# tinyblick2.net
KiCad netlist of a schematic drawn in EAGLE
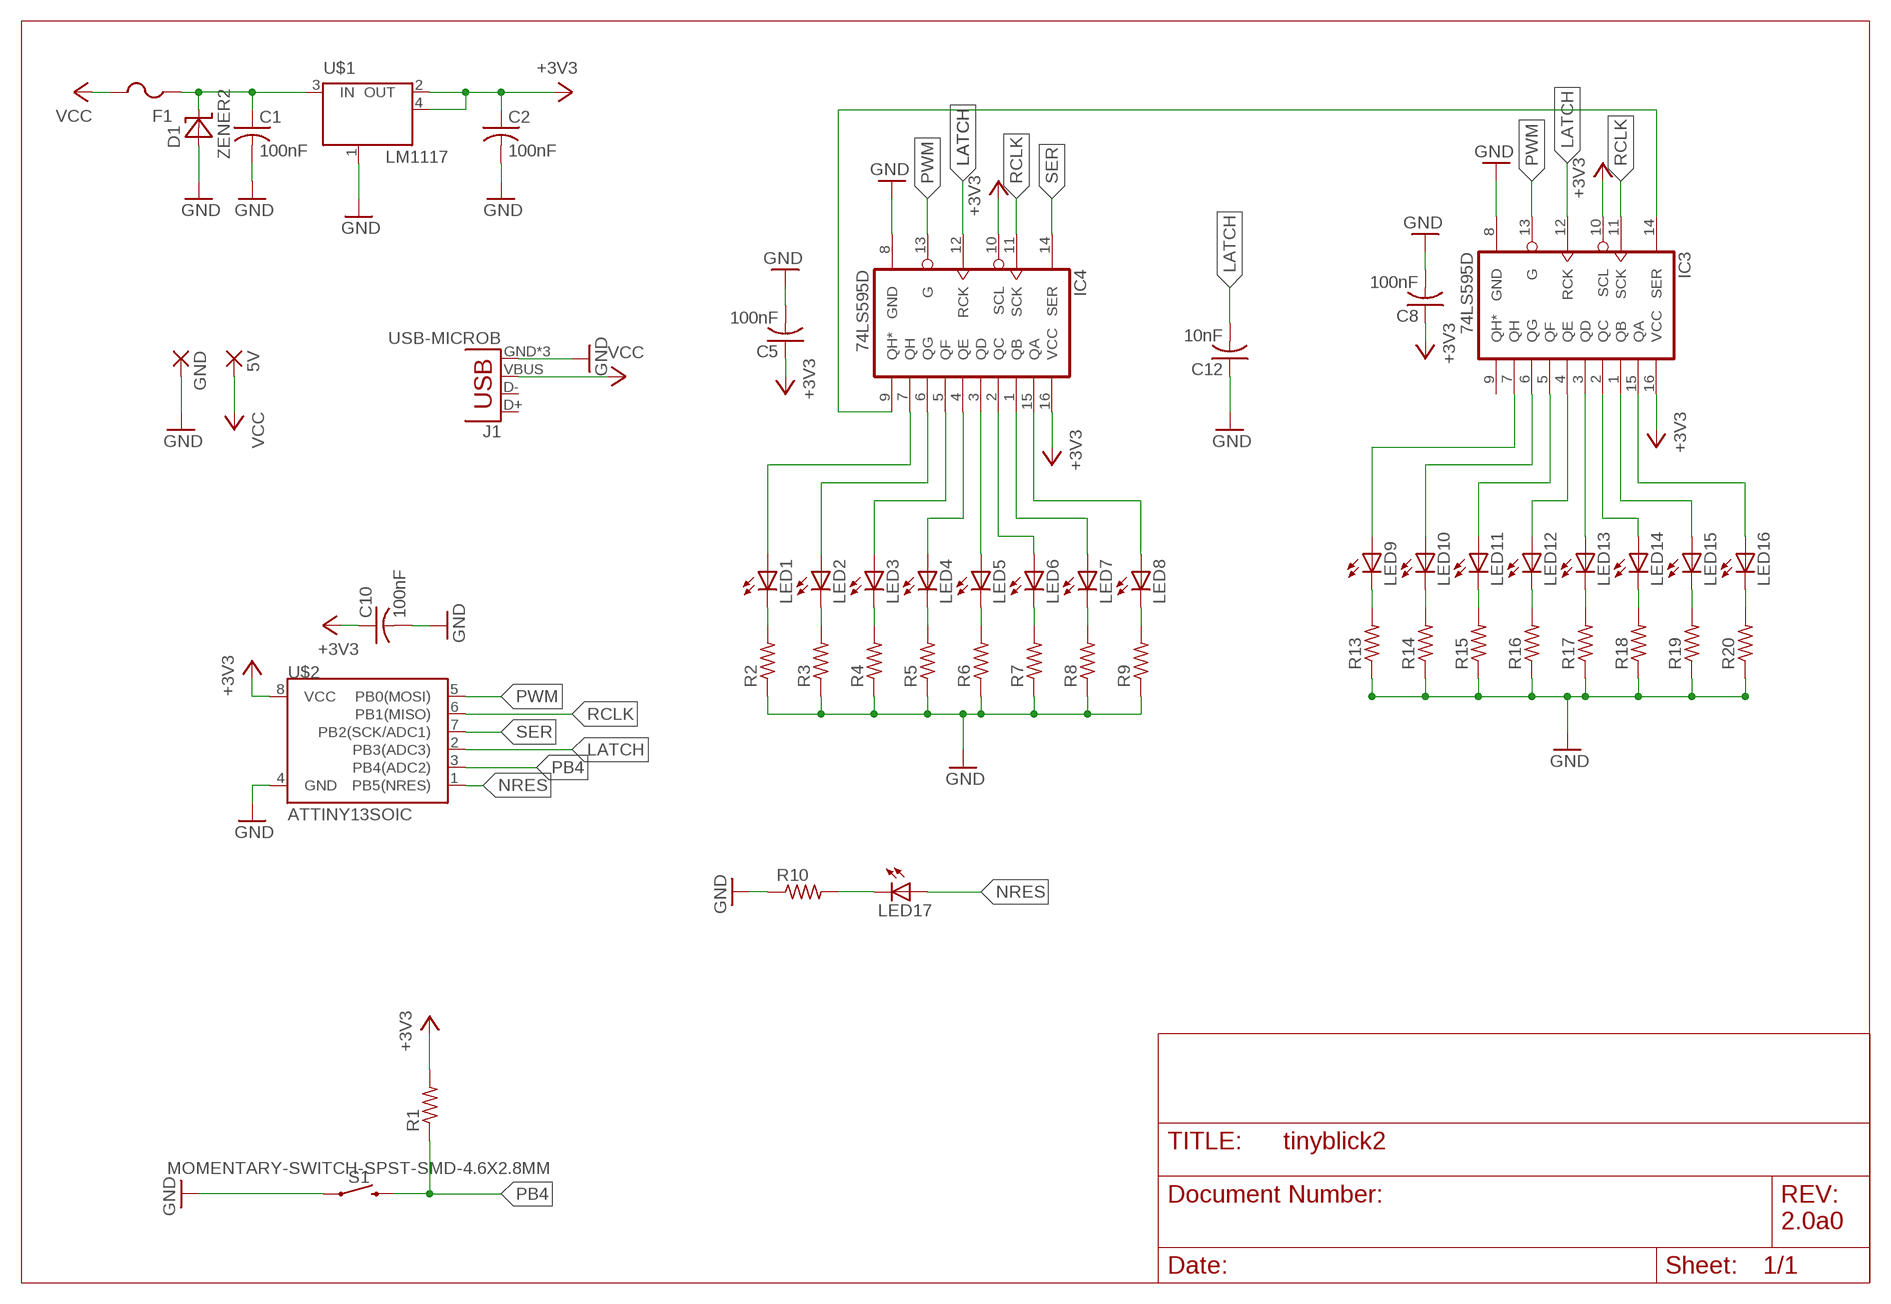
[diagram p0: schematic, sheet 1]

(export (version "E")
  (design (tool "Eeschema 10.0.6"))
  (components
    (comp (ref "5V")
      (value "WIREPADSMD2,54-5,08")
      (footprint "eagle-import:SMD2,54-5,08")
      (libsource (lib "eagle-import") (part "WIREPADSMD2,54-5,08"))
    )
    (comp (ref "C1")
      (value "100nF")
      (footprint "eagle-import:C0603")
      (libsource (lib "eagle-import") (part "C-USC0603"))
    )
    (comp (ref "C2")
      (value "100nF")
      (footprint "eagle-import:C0603")
      (libsource (lib "eagle-import") (part "C-USC0603"))
    )
    (comp (ref "C5")
      (value "100nF")
      (footprint "eagle-import:C0603")
      (libsource (lib "eagle-import") (part "C-USC0603"))
    )
    (comp (ref "C8")
      (value "100nF")
      (footprint "eagle-import:C0603")
      (libsource (lib "eagle-import") (part "C-USC0603"))
    )
    (comp (ref "C10")
      (value "100nF")
      (footprint "eagle-import:C0603")
      (libsource (lib "eagle-import") (part "C-USC0603"))
    )
    (comp (ref "C12")
      (value "10nF")
      (footprint "eagle-import:C0603")
      (libsource (lib "eagle-import") (part "C-USC0603"))
    )
    (comp (ref "D1")
      (value "ZENER2")
      (footprint "eagle-import:SOD123")
      (libsource (lib "eagle-import") (part "ZENER2"))
    )
    (comp (ref "F1")
      (value "PTCFUSE-1206")
      (footprint "eagle-import:R1206")
      (libsource (lib "eagle-import") (part "PTCFUSE-1206"))
    )
    (comp (ref "GND")
      (value "WIREPADSMD2,54-5,08")
      (footprint "eagle-import:SMD2,54-5,08")
      (libsource (lib "eagle-import") (part "WIREPADSMD2,54-5,08"))
    )
    (comp (ref "IC3")
      (value "74LS595D")
      (footprint "eagle-import:SO16")
      (libsource (lib "eagle-import") (part "74595DLS"))
    )
    (comp (ref "IC4")
      (value "74LS595D")
      (footprint "eagle-import:SO16")
      (fields (field (name "SPICEPREFIX") "X"))
      (libsource (lib "eagle-import") (part "74595DLS"))
    )
    (comp (ref "J1")
      (value "USB-MICROB")
      (footprint "eagle-import:USB-MICROB")
      (libsource (lib "eagle-import") (part "USB-MICROB"))
    )
    (comp (ref "LED1")
      (value "LEDCHIP-LED0603")
      (footprint "eagle-import:CHIP-LED0603")
      (libsource (lib "eagle-import") (part "LEDCHIP-LED0603"))
    )
    (comp (ref "LED2")
      (value "LEDCHIP-LED0603")
      (footprint "eagle-import:CHIP-LED0603")
      (libsource (lib "eagle-import") (part "LEDCHIP-LED0603"))
    )
    (comp (ref "LED3")
      (value "LEDCHIP-LED0603")
      (footprint "eagle-import:CHIP-LED0603")
      (libsource (lib "eagle-import") (part "LEDCHIP-LED0603"))
    )
    (comp (ref "LED4")
      (value "LEDCHIP-LED0603")
      (footprint "eagle-import:CHIP-LED0603")
      (libsource (lib "eagle-import") (part "LEDCHIP-LED0603"))
    )
    (comp (ref "LED5")
      (value "LEDCHIP-LED0603")
      (footprint "eagle-import:CHIP-LED0603")
      (libsource (lib "eagle-import") (part "LEDCHIP-LED0603"))
    )
    (comp (ref "LED6")
      (value "LEDCHIP-LED0603")
      (footprint "eagle-import:CHIP-LED0603")
      (libsource (lib "eagle-import") (part "LEDCHIP-LED0603"))
    )
    (comp (ref "LED7")
      (value "LEDCHIP-LED0603")
      (footprint "eagle-import:CHIP-LED0603")
      (libsource (lib "eagle-import") (part "LEDCHIP-LED0603"))
    )
    (comp (ref "LED8")
      (value "LEDCHIP-LED0603")
      (footprint "eagle-import:CHIP-LED0603")
      (libsource (lib "eagle-import") (part "LEDCHIP-LED0603"))
    )
    (comp (ref "LED9")
      (value "LEDCHIP-LED0603")
      (footprint "eagle-import:CHIP-LED0603")
      (libsource (lib "eagle-import") (part "LEDCHIP-LED0603"))
    )
    (comp (ref "LED10")
      (value "LEDCHIP-LED0603")
      (footprint "eagle-import:CHIP-LED0603")
      (libsource (lib "eagle-import") (part "LEDCHIP-LED0603"))
    )
    (comp (ref "LED11")
      (value "LEDCHIP-LED0603")
      (footprint "eagle-import:CHIP-LED0603")
      (libsource (lib "eagle-import") (part "LEDCHIP-LED0603"))
    )
    (comp (ref "LED12")
      (value "LEDCHIP-LED0603")
      (footprint "eagle-import:CHIP-LED0603")
      (libsource (lib "eagle-import") (part "LEDCHIP-LED0603"))
    )
    (comp (ref "LED13")
      (value "LEDCHIP-LED0603")
      (footprint "eagle-import:CHIP-LED0603")
      (libsource (lib "eagle-import") (part "LEDCHIP-LED0603"))
    )
    (comp (ref "LED14")
      (value "LEDCHIP-LED0603")
      (footprint "eagle-import:CHIP-LED0603")
      (libsource (lib "eagle-import") (part "LEDCHIP-LED0603"))
    )
    (comp (ref "LED15")
      (value "LEDCHIP-LED0603")
      (footprint "eagle-import:CHIP-LED0603")
      (libsource (lib "eagle-import") (part "LEDCHIP-LED0603"))
    )
    (comp (ref "LED16")
      (value "LEDCHIP-LED0603")
      (footprint "eagle-import:CHIP-LED0603")
      (libsource (lib "eagle-import") (part "LEDCHIP-LED0603"))
    )
    (comp (ref "LED17")
      (value "LEDCHIP-LED0603")
      (footprint "eagle-import:CHIP-LED0603")
      (libsource (lib "eagle-import") (part "LEDCHIP-LED0603"))
    )
    (comp (ref "R1")
      (value "R-US_R0603")
      (footprint "eagle-import:R0603")
      (libsource (lib "eagle-import") (part "R-US_R0603"))
    )
    (comp (ref "R2")
      (value "R-US_R0603")
      (footprint "eagle-import:R0603")
      (libsource (lib "eagle-import") (part "R-US_R0603"))
    )
    (comp (ref "R3")
      (value "R-US_R0603")
      (footprint "eagle-import:R0603")
      (libsource (lib "eagle-import") (part "R-US_R0603"))
    )
    (comp (ref "R4")
      (value "R-US_R0603")
      (footprint "eagle-import:R0603")
      (libsource (lib "eagle-import") (part "R-US_R0603"))
    )
    (comp (ref "R5")
      (value "R-US_R0603")
      (footprint "eagle-import:R0603")
      (libsource (lib "eagle-import") (part "R-US_R0603"))
    )
    (comp (ref "R6")
      (value "R-US_R0603")
      (footprint "eagle-import:R0603")
      (libsource (lib "eagle-import") (part "R-US_R0603"))
    )
    (comp (ref "R7")
      (value "R-US_R0603")
      (footprint "eagle-import:R0603")
      (libsource (lib "eagle-import") (part "R-US_R0603"))
    )
    (comp (ref "R8")
      (value "R-US_R0603")
      (footprint "eagle-import:R0603")
      (libsource (lib "eagle-import") (part "R-US_R0603"))
    )
    (comp (ref "R9")
      (value "R-US_R0603")
      (footprint "eagle-import:R0603")
      (libsource (lib "eagle-import") (part "R-US_R0603"))
    )
    (comp (ref "R10")
      (value "R-US_R0603")
      (footprint "eagle-import:R0603")
      (libsource (lib "eagle-import") (part "R-US_R0603"))
    )
    (comp (ref "R13")
      (value "R-US_R0603")
      (footprint "eagle-import:R0603")
      (libsource (lib "eagle-import") (part "R-US_R0603"))
    )
    (comp (ref "R14")
      (value "R-US_R0603")
      (footprint "eagle-import:R0603")
      (libsource (lib "eagle-import") (part "R-US_R0603"))
    )
    (comp (ref "R15")
      (value "R-US_R0603")
      (footprint "eagle-import:R0603")
      (libsource (lib "eagle-import") (part "R-US_R0603"))
    )
    (comp (ref "R16")
      (value "R-US_R0603")
      (footprint "eagle-import:R0603")
      (libsource (lib "eagle-import") (part "R-US_R0603"))
    )
    (comp (ref "R17")
      (value "R-US_R0603")
      (footprint "eagle-import:R0603")
      (libsource (lib "eagle-import") (part "R-US_R0603"))
    )
    (comp (ref "R18")
      (value "R-US_R0603")
      (footprint "eagle-import:R0603")
      (libsource (lib "eagle-import") (part "R-US_R0603"))
    )
    (comp (ref "R19")
      (value "R-US_R0603")
      (footprint "eagle-import:R0603")
      (libsource (lib "eagle-import") (part "R-US_R0603"))
    )
    (comp (ref "R20")
      (value "R-US_R0603")
      (footprint "eagle-import:R0603")
      (libsource (lib "eagle-import") (part "R-US_R0603"))
    )
    (comp (ref "S1")
      (value "MOMENTARY-SWITCH-SPST-SMD-4.6X2.8MM")
      (footprint "eagle-import:TACTILE_SWITCH_SMD_4.6X2.8MM")
      (libsource (lib "eagle-import") (part "MOMENTARY-SWITCH-SPST-SMD-4.6X2.8MM"))
    )
    (comp (ref "U$1")
      (value "LM1117")
      (footprint "eagle-import:SOT223")
      (libsource (lib "eagle-import") (part "LM1117"))
    )
    (comp (ref "U$2")
      (value "ATTINY13SOIC")
      (footprint "eagle-import:SO08")
      (libsource (lib "eagle-import") (part "ATTINY13SOIC"))
    )
  )
  (nets
    (net (code "1") (name "+3V3") (class "Default")
      (node (ref "C10") (pin "1") (pinfunction "1_1") (pintype "passive"))
      (node (ref "C2") (pin "1") (pinfunction "1_1") (pintype "passive"))
      (node (ref "C5") (pin "1") (pinfunction "1_1") (pintype "passive"))
      (node (ref "C8") (pin "1") (pinfunction "1_1") (pintype "passive"))
      (node (ref "IC3") (pin "10") (pinfunction "SCL_10") (pintype "input"))
      (node (ref "IC3") (pin "16") (pinfunction "VCC_16") (pintype "power_in"))
      (node (ref "IC4") (pin "10") (pinfunction "SCL_10") (pintype "input"))
      (node (ref "IC4") (pin "16") (pinfunction "VCC_16") (pintype "power_in"))
      (node (ref "R1") (pin "2") (pinfunction "2_2") (pintype "passive"))
      (node (ref "U$1") (pin "2") (pinfunction "OUT_2") (pintype "passive"))
      (node (ref "U$1") (pin "4") (pinfunction "OUT_4") (pintype "passive"))
      (node (ref "U$2") (pin "8") (pinfunction "VCC_8") (pintype "bidirectional"))
    )
    (net (code "2") (name "GND") (class "Default")
      (node (ref "C1") (pin "2") (pinfunction "2_2") (pintype "passive"))
      (node (ref "C10") (pin "2") (pinfunction "2_2") (pintype "passive"))
      (node (ref "C12") (pin "1") (pinfunction "1_1") (pintype "passive"))
      (node (ref "C2") (pin "2") (pinfunction "2_2") (pintype "passive"))
      (node (ref "C5") (pin "2") (pinfunction "2_2") (pintype "passive"))
      (node (ref "C8") (pin "2") (pinfunction "2_2") (pintype "passive"))
      (node (ref "D1") (pin "A") (pinfunction "A_A") (pintype "passive"))
      (node (ref "GND") (pin "1") (pinfunction "P_1") (pintype "passive"))
      (node (ref "IC3") (pin "8") (pinfunction "GND_8") (pintype "power_in"))
      (node (ref "IC4") (pin "8") (pinfunction "GND_8") (pintype "power_in"))
      (node (ref "J1") (pin "GND") (pinfunction "GND_GND") (pintype "bidirectional"))
      (node (ref "J1") (pin "MT1") (pinfunction "GND_MT1") (pintype "bidirectional"))
      (node (ref "J1") (pin "MT2") (pinfunction "GND_MT2") (pintype "bidirectional"))
      (node (ref "R10") (pin "1") (pinfunction "1_1") (pintype "passive"))
      (node (ref "R13") (pin "1") (pinfunction "1_1") (pintype "passive"))
      (node (ref "R14") (pin "1") (pinfunction "1_1") (pintype "passive"))
      (node (ref "R15") (pin "1") (pinfunction "1_1") (pintype "passive"))
      (node (ref "R16") (pin "1") (pinfunction "1_1") (pintype "passive"))
      (node (ref "R17") (pin "1") (pinfunction "1_1") (pintype "passive"))
      (node (ref "R18") (pin "1") (pinfunction "1_1") (pintype "passive"))
      (node (ref "R19") (pin "1") (pinfunction "1_1") (pintype "passive"))
      (node (ref "R2") (pin "1") (pinfunction "1_1") (pintype "passive"))
      (node (ref "R20") (pin "1") (pinfunction "1_1") (pintype "passive"))
      (node (ref "R3") (pin "1") (pinfunction "1_1") (pintype "passive"))
      (node (ref "R4") (pin "1") (pinfunction "1_1") (pintype "passive"))
      (node (ref "R5") (pin "1") (pinfunction "1_1") (pintype "passive"))
      (node (ref "R6") (pin "1") (pinfunction "1_1") (pintype "passive"))
      (node (ref "R7") (pin "1") (pinfunction "1_1") (pintype "passive"))
      (node (ref "R8") (pin "1") (pinfunction "1_1") (pintype "passive"))
      (node (ref "R9") (pin "1") (pinfunction "1_1") (pintype "passive"))
      (node (ref "S1") (pin "1") (pinfunction "1_1") (pintype "passive"))
      (node (ref "S1") (pin "2") (pinfunction "1_2") (pintype "passive"))
      (node (ref "U$1") (pin "1") (pinfunction "GND/ADJ_1") (pintype "input"))
      (node (ref "U$2") (pin "4") (pinfunction "GND_4") (pintype "bidirectional"))
    )
    (net (code "3") (name "LATCH") (class "Default")
      (node (ref "C12") (pin "2") (pinfunction "2_2") (pintype "passive"))
      (node (ref "IC3") (pin "12") (pinfunction "RCK_12") (pintype "input"))
      (node (ref "IC4") (pin "12") (pinfunction "RCK_12") (pintype "input"))
      (node (ref "U$2") (pin "2") (pinfunction "PB3(ADC3)_2") (pintype "bidirectional"))
    )
    (net (code "4") (name "NRES") (class "Default")
      (node (ref "LED17") (pin "A") (pinfunction "A_A") (pintype "passive"))
      (node (ref "U$2") (pin "1") (pinfunction "PB5(NRES)_1") (pintype "bidirectional"))
    )
    (net (code "5") (name "Net-(IC3-QA)") (class "Default")
      (node (ref "IC3") (pin "15") (pinfunction "QA_15") (pintype "tri_state"))
      (node (ref "LED16") (pin "A") (pinfunction "A_A") (pintype "passive"))
    )
    (net (code "6") (name "Net-(IC3-QB)") (class "Default")
      (node (ref "IC3") (pin "1") (pinfunction "QB_1") (pintype "tri_state"))
      (node (ref "LED15") (pin "A") (pinfunction "A_A") (pintype "passive"))
    )
    (net (code "7") (name "Net-(IC3-QC)") (class "Default")
      (node (ref "IC3") (pin "2") (pinfunction "QC_2") (pintype "tri_state"))
      (node (ref "LED14") (pin "A") (pinfunction "A_A") (pintype "passive"))
    )
    (net (code "8") (name "Net-(IC3-QD)") (class "Default")
      (node (ref "IC3") (pin "3") (pinfunction "QD_3") (pintype "tri_state"))
      (node (ref "LED13") (pin "A") (pinfunction "A_A") (pintype "passive"))
    )
    (net (code "9") (name "Net-(IC3-QE)") (class "Default")
      (node (ref "IC3") (pin "4") (pinfunction "QE_4") (pintype "tri_state"))
      (node (ref "LED12") (pin "A") (pinfunction "A_A") (pintype "passive"))
    )
    (net (code "10") (name "Net-(IC3-QF)") (class "Default")
      (node (ref "IC3") (pin "5") (pinfunction "QF_5") (pintype "tri_state"))
      (node (ref "LED11") (pin "A") (pinfunction "A_A") (pintype "passive"))
    )
    (net (code "11") (name "Net-(IC3-QG)") (class "Default")
      (node (ref "IC3") (pin "6") (pinfunction "QG_6") (pintype "tri_state"))
      (node (ref "LED10") (pin "A") (pinfunction "A_A") (pintype "passive"))
    )
    (net (code "12") (name "Net-(IC3-QH)") (class "Default")
      (node (ref "IC3") (pin "7") (pinfunction "QH_7") (pintype "tri_state"))
      (node (ref "LED9") (pin "A") (pinfunction "A_A") (pintype "passive"))
    )
    (net (code "13") (name "Net-(IC3-SER)") (class "Default")
      (node (ref "IC3") (pin "14") (pinfunction "SER_14") (pintype "input"))
      (node (ref "IC4") (pin "9") (pinfunction "QH*_9") (pintype "tri_state"))
    )
    (net (code "14") (name "Net-(IC4-QA)") (class "Default")
      (node (ref "IC4") (pin "15") (pinfunction "QA_15") (pintype "tri_state"))
      (node (ref "LED8") (pin "A") (pinfunction "A_A") (pintype "passive"))
    )
    (net (code "15") (name "Net-(IC4-QB)") (class "Default")
      (node (ref "IC4") (pin "1") (pinfunction "QB_1") (pintype "tri_state"))
      (node (ref "LED7") (pin "A") (pinfunction "A_A") (pintype "passive"))
    )
    (net (code "16") (name "Net-(IC4-QC)") (class "Default")
      (node (ref "IC4") (pin "2") (pinfunction "QC_2") (pintype "tri_state"))
      (node (ref "LED6") (pin "A") (pinfunction "A_A") (pintype "passive"))
    )
    (net (code "17") (name "Net-(IC4-QD)") (class "Default")
      (node (ref "IC4") (pin "3") (pinfunction "QD_3") (pintype "tri_state"))
      (node (ref "LED5") (pin "A") (pinfunction "A_A") (pintype "passive"))
    )
    (net (code "18") (name "Net-(IC4-QE)") (class "Default")
      (node (ref "IC4") (pin "4") (pinfunction "QE_4") (pintype "tri_state"))
      (node (ref "LED4") (pin "A") (pinfunction "A_A") (pintype "passive"))
    )
    (net (code "19") (name "Net-(IC4-QF)") (class "Default")
      (node (ref "IC4") (pin "5") (pinfunction "QF_5") (pintype "tri_state"))
      (node (ref "LED3") (pin "A") (pinfunction "A_A") (pintype "passive"))
    )
    (net (code "20") (name "Net-(IC4-QG)") (class "Default")
      (node (ref "IC4") (pin "6") (pinfunction "QG_6") (pintype "tri_state"))
      (node (ref "LED2") (pin "A") (pinfunction "A_A") (pintype "passive"))
    )
    (net (code "21") (name "Net-(IC4-QH)") (class "Default")
      (node (ref "IC4") (pin "7") (pinfunction "QH_7") (pintype "tri_state"))
      (node (ref "LED1") (pin "A") (pinfunction "A_A") (pintype "passive"))
    )
    (net (code "22") (name "Net-(LED1-PadC)") (class "Default")
      (node (ref "LED1") (pin "C") (pinfunction "C_C") (pintype "passive"))
      (node (ref "R2") (pin "2") (pinfunction "2_2") (pintype "passive"))
    )
    (net (code "23") (name "Net-(LED2-PadC)") (class "Default")
      (node (ref "LED2") (pin "C") (pinfunction "C_C") (pintype "passive"))
      (node (ref "R3") (pin "2") (pinfunction "2_2") (pintype "passive"))
    )
    (net (code "24") (name "Net-(LED3-PadC)") (class "Default")
      (node (ref "LED3") (pin "C") (pinfunction "C_C") (pintype "passive"))
      (node (ref "R4") (pin "2") (pinfunction "2_2") (pintype "passive"))
    )
    (net (code "25") (name "Net-(LED4-PadC)") (class "Default")
      (node (ref "LED4") (pin "C") (pinfunction "C_C") (pintype "passive"))
      (node (ref "R5") (pin "2") (pinfunction "2_2") (pintype "passive"))
    )
    (net (code "26") (name "Net-(LED5-PadC)") (class "Default")
      (node (ref "LED5") (pin "C") (pinfunction "C_C") (pintype "passive"))
      (node (ref "R6") (pin "2") (pinfunction "2_2") (pintype "passive"))
    )
    (net (code "27") (name "Net-(LED6-PadC)") (class "Default")
      (node (ref "LED6") (pin "C") (pinfunction "C_C") (pintype "passive"))
      (node (ref "R7") (pin "2") (pinfunction "2_2") (pintype "passive"))
    )
    (net (code "28") (name "Net-(LED7-PadC)") (class "Default")
      (node (ref "LED7") (pin "C") (pinfunction "C_C") (pintype "passive"))
      (node (ref "R8") (pin "2") (pinfunction "2_2") (pintype "passive"))
    )
    (net (code "29") (name "Net-(LED8-PadC)") (class "Default")
      (node (ref "LED8") (pin "C") (pinfunction "C_C") (pintype "passive"))
      (node (ref "R9") (pin "2") (pinfunction "2_2") (pintype "passive"))
    )
    (net (code "30") (name "Net-(LED9-PadC)") (class "Default")
      (node (ref "LED9") (pin "C") (pinfunction "C_C") (pintype "passive"))
      (node (ref "R13") (pin "2") (pinfunction "2_2") (pintype "passive"))
    )
    (net (code "31") (name "Net-(LED10-PadC)") (class "Default")
      (node (ref "LED10") (pin "C") (pinfunction "C_C") (pintype "passive"))
      (node (ref "R14") (pin "2") (pinfunction "2_2") (pintype "passive"))
    )
    (net (code "32") (name "Net-(LED11-PadC)") (class "Default")
      (node (ref "LED11") (pin "C") (pinfunction "C_C") (pintype "passive"))
      (node (ref "R15") (pin "2") (pinfunction "2_2") (pintype "passive"))
    )
    (net (code "33") (name "Net-(LED12-PadC)") (class "Default")
      (node (ref "LED12") (pin "C") (pinfunction "C_C") (pintype "passive"))
      (node (ref "R16") (pin "2") (pinfunction "2_2") (pintype "passive"))
    )
    (net (code "34") (name "Net-(LED13-PadC)") (class "Default")
      (node (ref "LED13") (pin "C") (pinfunction "C_C") (pintype "passive"))
      (node (ref "R17") (pin "2") (pinfunction "2_2") (pintype "passive"))
    )
    (net (code "35") (name "Net-(LED14-PadC)") (class "Default")
      (node (ref "LED14") (pin "C") (pinfunction "C_C") (pintype "passive"))
      (node (ref "R18") (pin "2") (pinfunction "2_2") (pintype "passive"))
    )
    (net (code "36") (name "Net-(LED15-PadC)") (class "Default")
      (node (ref "LED15") (pin "C") (pinfunction "C_C") (pintype "passive"))
      (node (ref "R19") (pin "2") (pinfunction "2_2") (pintype "passive"))
    )
    (net (code "37") (name "Net-(LED16-PadC)") (class "Default")
      (node (ref "LED16") (pin "C") (pinfunction "C_C") (pintype "passive"))
      (node (ref "R20") (pin "2") (pinfunction "2_2") (pintype "passive"))
    )
    (net (code "38") (name "Net-(LED17-PadC)") (class "Default")
      (node (ref "LED17") (pin "C") (pinfunction "C_C") (pintype "passive"))
      (node (ref "R10") (pin "2") (pinfunction "2_2") (pintype "passive"))
    )
    (net (code "39") (name "Net-(U$1-IN)") (class "Default")
      (node (ref "C1") (pin "1") (pinfunction "1_1") (pintype "passive"))
      (node (ref "D1") (pin "C") (pinfunction "C_C") (pintype "passive"))
      (node (ref "F1") (pin "1") (pinfunction "1_1") (pintype "passive"))
      (node (ref "U$1") (pin "3") (pinfunction "IN_3") (pintype "input"))
    )
    (net (code "40") (name "PB4") (class "Default")
      (node (ref "R1") (pin "1") (pinfunction "1_1") (pintype "passive"))
      (node (ref "S1") (pin "3") (pinfunction "2_3") (pintype "passive"))
      (node (ref "S1") (pin "4") (pinfunction "2_4") (pintype "passive"))
      (node (ref "U$2") (pin "3") (pinfunction "PB4(ADC2)_3") (pintype "bidirectional"))
    )
    (net (code "41") (name "PWM") (class "Default")
      (node (ref "IC3") (pin "13") (pinfunction "G_13") (pintype "input"))
      (node (ref "IC4") (pin "13") (pinfunction "G_13") (pintype "input"))
      (node (ref "U$2") (pin "5") (pinfunction "PB0(MOSI)_5") (pintype "bidirectional"))
    )
    (net (code "42") (name "RCLK") (class "Default")
      (node (ref "IC3") (pin "11") (pinfunction "SCK_11") (pintype "input"))
      (node (ref "IC4") (pin "11") (pinfunction "SCK_11") (pintype "input"))
      (node (ref "U$2") (pin "6") (pinfunction "PB1(MISO)_6") (pintype "bidirectional"))
    )
    (net (code "43") (name "SER") (class "Default")
      (node (ref "IC4") (pin "14") (pinfunction "SER_14") (pintype "input"))
      (node (ref "U$2") (pin "7") (pinfunction "PB2(SCK/ADC1)_7") (pintype "bidirectional"))
    )
    (net (code "44") (name "VCC") (class "Default")
      (node (ref "5V") (pin "1") (pinfunction "P_1") (pintype "passive"))
      (node (ref "F1") (pin "2") (pinfunction "2_2") (pintype "passive"))
      (node (ref "J1") (pin "VBUS") (pinfunction "VBUS_VBUS") (pintype "bidirectional"))
    )
    (net (code "45") (name "unconnected-(IC3-QH*-Pad9)") (class "Default")
      (node (ref "IC3") (pin "9") (pinfunction "QH*_9") (pintype "tri_state"))
    )
    (net (code "46") (name "unconnected-(J1-PadD+)") (class "Default")
      (node (ref "J1") (pin "D+") (pinfunction "D+_D+") (pintype "bidirectional"))
    )
    (net (code "47") (name "unconnected-(J1-PadD-)") (class "Default")
      (node (ref "J1") (pin "D-") (pinfunction "D-_D-") (pintype "bidirectional"))
    )
  )
)
